# 04_-_Power.net
KiCad netlist of a schematic drawn in Altium Designer
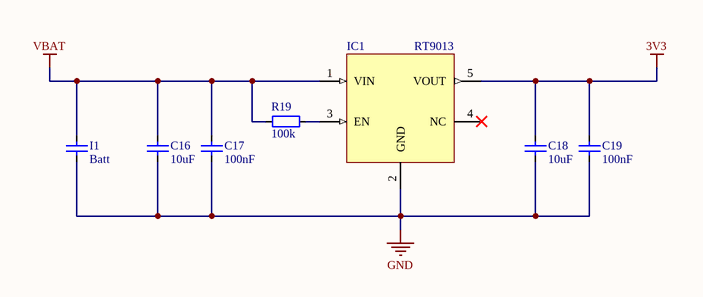
[diagram p0: [04] - Power.SchDoc]

(export (version "E")
  (design (tool "Eeschema 10.0.6"))
  (components
    (comp (ref "C16")
      (value "10uF")
      (footprint "CAP_0603")
      (description "Capacitor")
      (fields (field (name "PUBLISHER") "Altium Limited"))
      (libsource (lib "My Library") (part "CapSMD"))
    )
    (comp (ref "C17")
      (value "100nF")
      (footprint "CAP_0603")
      (description "Capacitor")
      (fields (field (name "PUBLISHER") "Altium Limited"))
      (libsource (lib "My Library") (part "CapSMD"))
    )
    (comp (ref "C18")
      (value "10uF")
      (footprint "CAP_0603")
      (description "Capacitor")
      (fields (field (name "PUBLISHER") "Altium Limited"))
      (libsource (lib "My Library") (part "CapSMD"))
    )
    (comp (ref "C19")
      (value "100nF")
      (footprint "CAP_0603")
      (description "Capacitor")
      (fields (field (name "PUBLISHER") "Altium Limited"))
      (libsource (lib "My Library") (part "CapSMD"))
    )
    (comp (ref "I1")
      (value "Batt")
      (footprint "CAP_3216")
      (description "Pad")
      (fields (field (name "PUBLISHER") "Altium Limited"))
      (libsource (lib "My Library") (part "CapSMD"))
    )
    (comp (ref "IC1")
      (value "RT9013")
      (footprint "SOT23-5")
      (description "RT9013-33GB IC REG LINEAR 3.3V 500mA SOT23-5")
      (libsource (lib "My Library") (part "RT9013"))
    )
    (comp (ref "R19")
      (value "100k")
      (footprint "RES-SMD-0603")
      (description "Resistor")
      (fields
        (field (name "MANUFACTURER") "Generic Components")
        (field (name "PUBLISHER") "Altium Hobart Technology Centre")
      )
      (libsource (lib "My Library") (part "Resistor - SMD"))
    )
  )
  (nets
    (net (code "1") (name "3V3") (class "Default")
      (node (ref "C18") (pin "2") (pinfunction "2_2") (pintype "passive"))
      (node (ref "C19") (pin "2") (pinfunction "2_2") (pintype "passive"))
      (node (ref "IC1") (pin "5") (pinfunction "VOUT_5") (pintype "output"))
    )
    (net (code "2") (name "GND") (class "Default")
      (node (ref "C16") (pin "1") (pinfunction "1_1") (pintype "passive"))
      (node (ref "C17") (pin "1") (pinfunction "1_1") (pintype "passive"))
      (node (ref "C18") (pin "1") (pinfunction "1_1") (pintype "passive"))
      (node (ref "C19") (pin "1") (pinfunction "1_1") (pintype "passive"))
      (node (ref "I1") (pin "1") (pinfunction "1_1") (pintype "passive"))
      (node (ref "IC1") (pin "2") (pinfunction "GND_2") (pintype "passive"))
    )
    (net (code "3") (name "Net-(IC1-EN)") (class "Default")
      (node (ref "IC1") (pin "3") (pinfunction "EN_3") (pintype "input"))
      (node (ref "R19") (pin "1") (pinfunction "1_1") (pintype "passive"))
    )
    (net (code "4") (name "VBAT") (class "Default")
      (node (ref "C16") (pin "2") (pinfunction "2_2") (pintype "passive"))
      (node (ref "C17") (pin "2") (pinfunction "2_2") (pintype "passive"))
      (node (ref "I1") (pin "2") (pinfunction "2_2") (pintype "passive"))
      (node (ref "IC1") (pin "1") (pinfunction "VIN_1") (pintype "input"))
      (node (ref "R19") (pin "2") (pinfunction "2_2") (pintype "passive"))
    )
    (net (code "5") (name "unconnected-(IC1-NC-Pad4)") (class "Default")
      (node (ref "IC1") (pin "4") (pinfunction "NC_4") (pintype "passive+no_connect"))
    )
  )
)
